# PMactrix.net
KiCad netlist of a schematic drawn in EasyEDA Pro
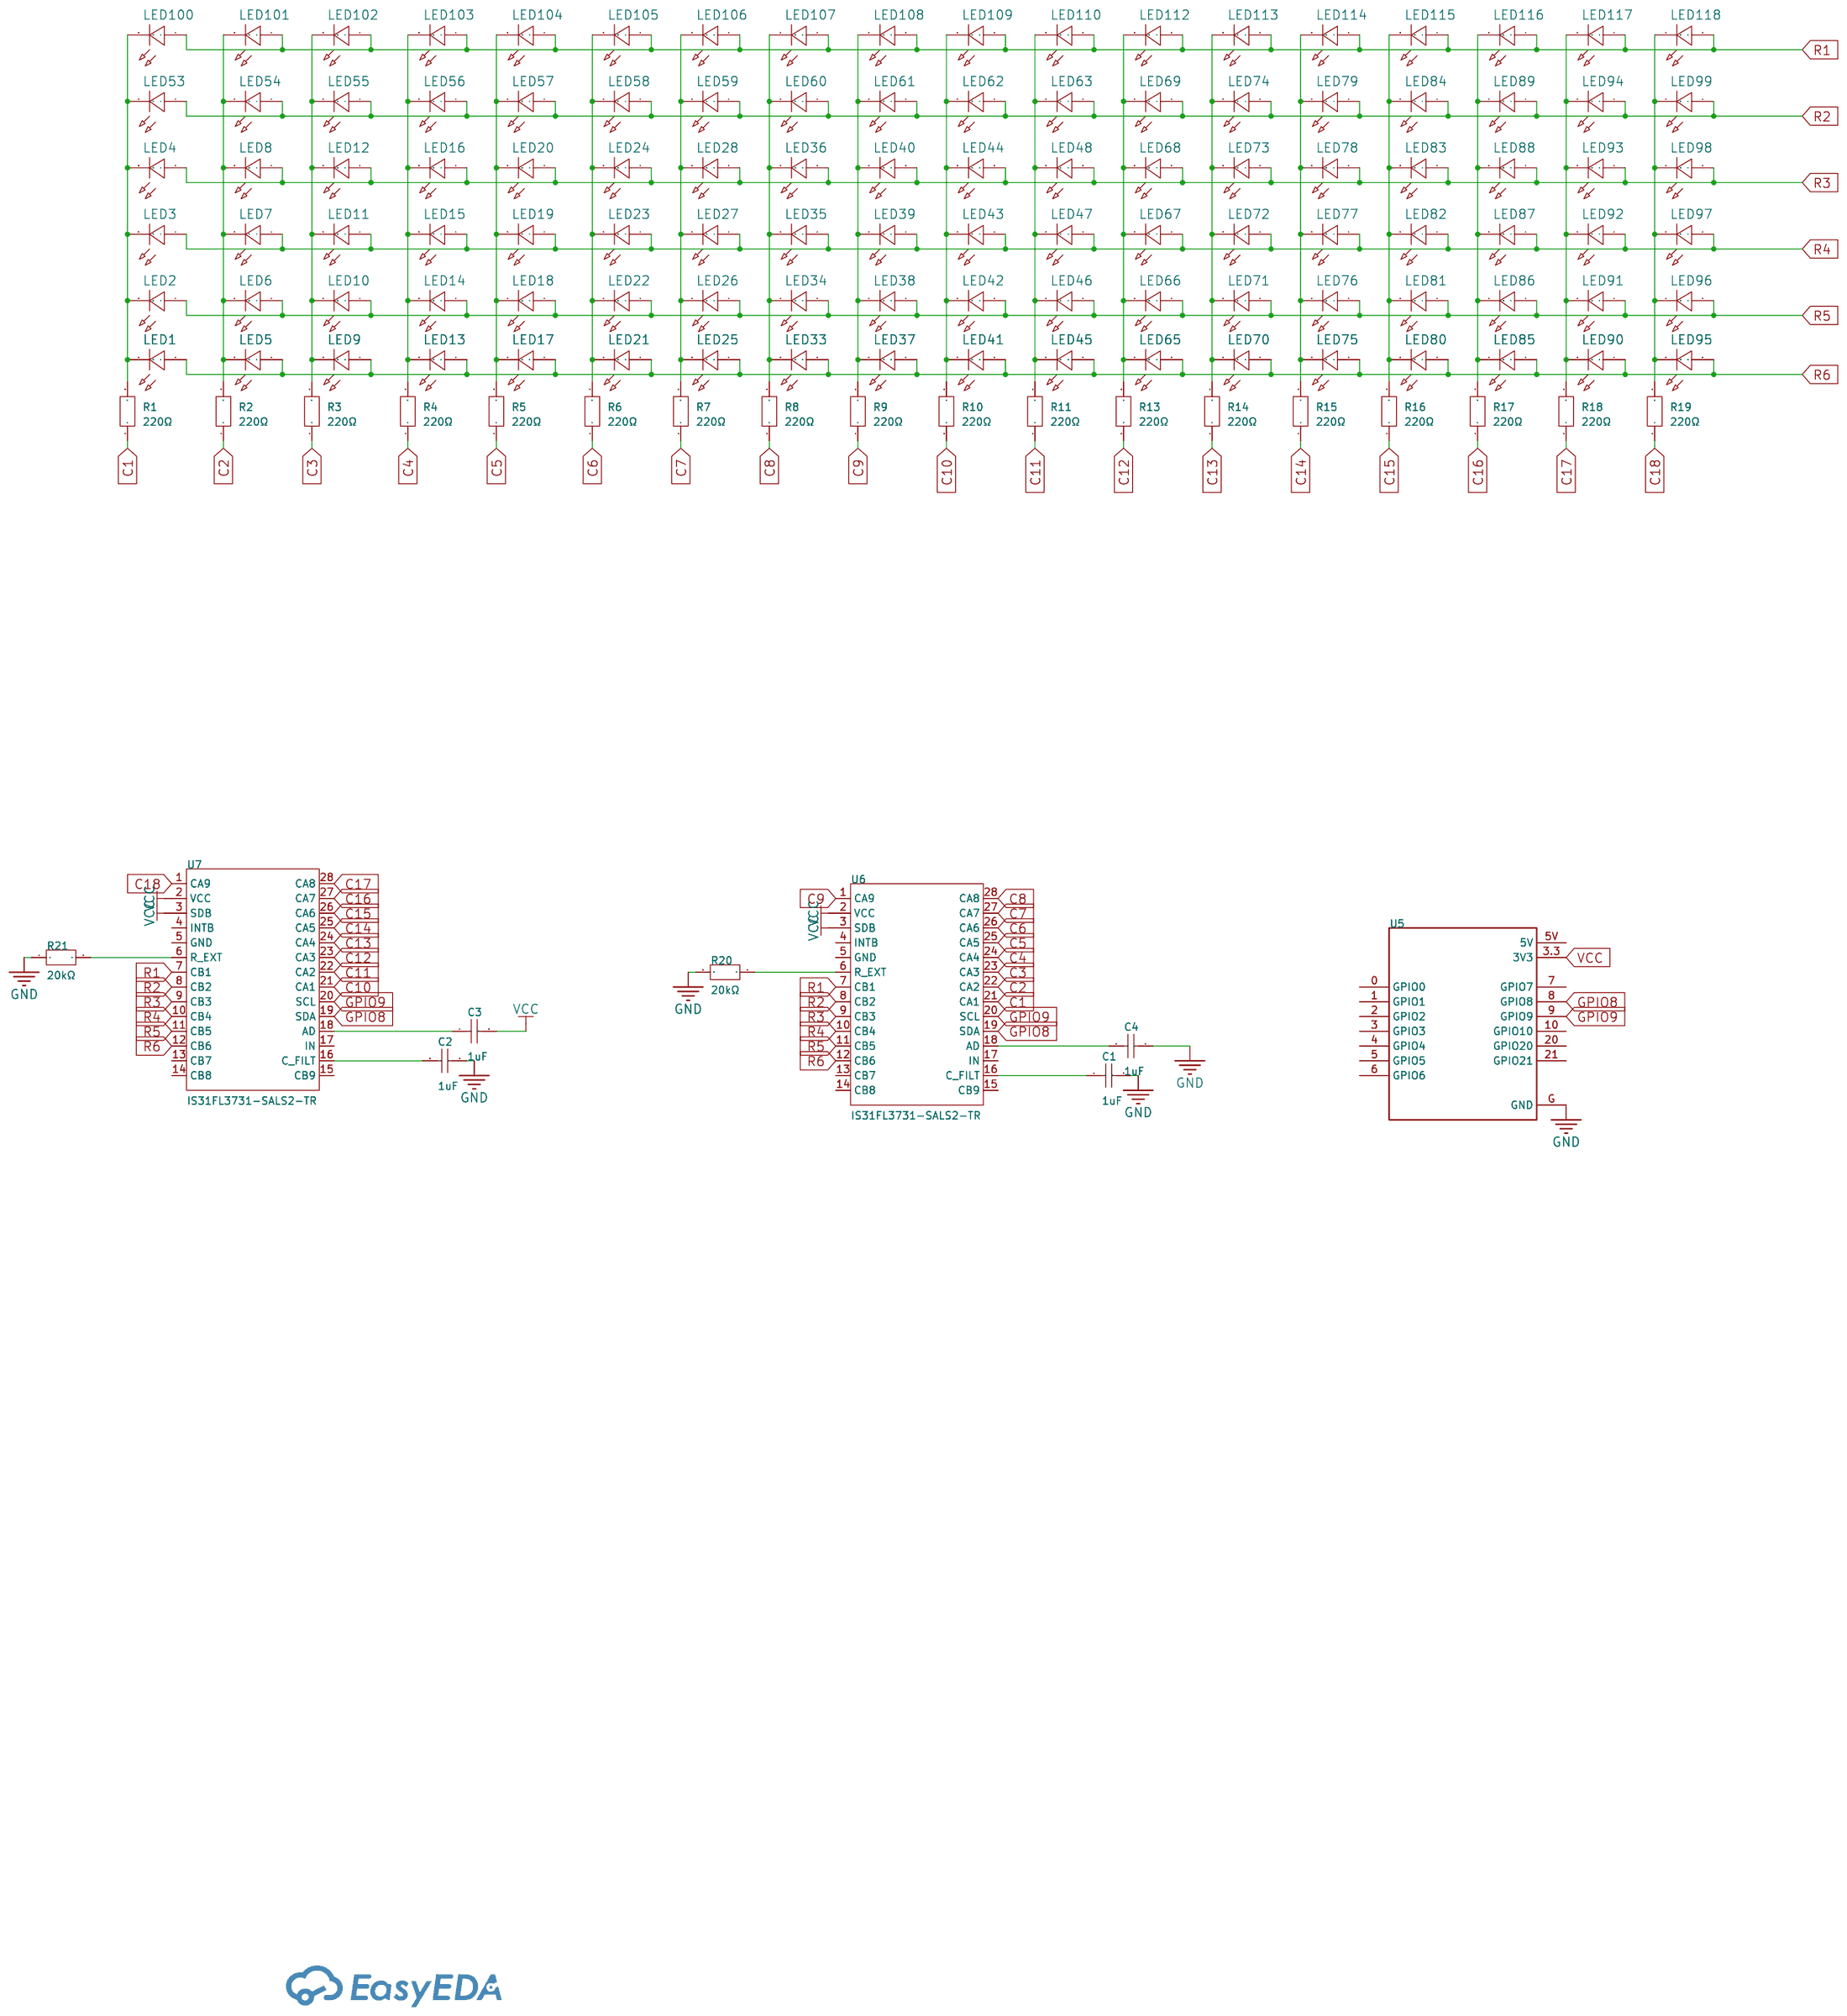
[diagram p0: schematic sheet]

(export (version "E")
  (design (tool "Eeschema 10.0.6"))
  (components
    (comp (ref "C1")
      (value "1uF")
      (footprint "easyedapro:C0603")
      (description "Capacitance:1uF Tolerance:±10% Tolerance:±10% Voltage Rating:25V Temperature Coefficient:X7R")
      (fields
        (field (name "Manufacturer Part") "CL10B105KA8NNNC")
        (field (name "Manufacturer") "SAMSUNG(三星)")
      )
      (libsource (lib "easyedapro") (part "CL10B105KA8NNNC"))
    )
    (comp (ref "C2")
      (value "1uF")
      (footprint "easyedapro:C0603")
      (description "Capacitance:1uF Tolerance:±10% Tolerance:±10% Voltage Rating:25V Temperature Coefficient:X7R")
      (fields
        (field (name "Manufacturer Part") "CL10B105KA8NNNC")
        (field (name "Manufacturer") "SAMSUNG(三星)")
      )
      (libsource (lib "easyedapro") (part "CL10B105KA8NNNC"))
    )
    (comp (ref "C3")
      (value "1uF")
      (footprint "easyedapro:C0603")
      (description "Capacitance:1uF Tolerance:±10% Tolerance:±10% Voltage Rating:25V Temperature Coefficient:X7R")
      (fields
        (field (name "Manufacturer Part") "CL10B105KA8NNNC")
        (field (name "Manufacturer") "SAMSUNG(三星)")
      )
      (libsource (lib "easyedapro") (part "CL10B105KA8NNNC"))
    )
    (comp (ref "C4")
      (value "1uF")
      (footprint "easyedapro:C0603")
      (description "Capacitance:1uF Tolerance:±10% Tolerance:±10% Voltage Rating:25V Temperature Coefficient:X7R")
      (fields
        (field (name "Manufacturer Part") "CL10B105KA8NNNC")
        (field (name "Manufacturer") "SAMSUNG(三星)")
      )
      (libsource (lib "easyedapro") (part "CL10B105KA8NNNC"))
    )
    (comp (ref "LED1")
      (value "SZYY0603W")
      (footprint "easyedapro:LED0402-RD_YELLOW")
      (fields (field (name "Manufacturer") "yongyu(永裕光电)"))
      (libsource (lib "easyedapro") (part "LED_R"))
    )
    (comp (ref "LED2")
      (value "SZYY0603W")
      (footprint "easyedapro:LED0402-RD_YELLOW")
      (fields (field (name "Manufacturer") "yongyu(永裕光电)"))
      (libsource (lib "easyedapro") (part "LED_R"))
    )
    (comp (ref "LED3")
      (value "SZYY0603W")
      (footprint "easyedapro:LED0402-RD_YELLOW")
      (fields (field (name "Manufacturer") "yongyu(永裕光电)"))
      (libsource (lib "easyedapro") (part "LED_R"))
    )
    (comp (ref "LED4")
      (value "SZYY0603W")
      (footprint "easyedapro:LED0402-RD_YELLOW")
      (fields (field (name "Manufacturer") "yongyu(永裕光电)"))
      (libsource (lib "easyedapro") (part "LED_R"))
    )
    (comp (ref "LED5")
      (value "SZYY0603W")
      (footprint "easyedapro:LED0402-RD_YELLOW")
      (fields (field (name "Manufacturer") "yongyu(永裕光电)"))
      (libsource (lib "easyedapro") (part "LED_R"))
    )
    (comp (ref "LED6")
      (value "SZYY0603W")
      (footprint "easyedapro:LED0402-RD_YELLOW")
      (fields (field (name "Manufacturer") "yongyu(永裕光电)"))
      (libsource (lib "easyedapro") (part "LED_R"))
    )
    (comp (ref "LED7")
      (value "SZYY0603W")
      (footprint "easyedapro:LED0402-RD_YELLOW")
      (fields (field (name "Manufacturer") "yongyu(永裕光电)"))
      (libsource (lib "easyedapro") (part "LED_R"))
    )
    (comp (ref "LED8")
      (value "SZYY0603W")
      (footprint "easyedapro:LED0402-RD_YELLOW")
      (fields (field (name "Manufacturer") "yongyu(永裕光电)"))
      (libsource (lib "easyedapro") (part "LED_R"))
    )
    (comp (ref "LED9")
      (value "SZYY0603W")
      (footprint "easyedapro:LED0402-RD_YELLOW")
      (fields (field (name "Manufacturer") "yongyu(永裕光电)"))
      (libsource (lib "easyedapro") (part "LED_R"))
    )
    (comp (ref "LED10")
      (value "SZYY0603W")
      (footprint "easyedapro:LED0402-RD_YELLOW")
      (fields (field (name "Manufacturer") "yongyu(永裕光电)"))
      (libsource (lib "easyedapro") (part "LED_R"))
    )
    (comp (ref "LED11")
      (value "SZYY0603W")
      (footprint "easyedapro:LED0402-RD_YELLOW")
      (fields (field (name "Manufacturer") "yongyu(永裕光电)"))
      (libsource (lib "easyedapro") (part "LED_R"))
    )
    (comp (ref "LED12")
      (value "SZYY0603W")
      (footprint "easyedapro:LED0402-RD_YELLOW")
      (fields (field (name "Manufacturer") "yongyu(永裕光电)"))
      (libsource (lib "easyedapro") (part "LED_R"))
    )
    (comp (ref "LED13")
      (value "SZYY0603W")
      (footprint "easyedapro:LED0402-RD_YELLOW")
      (fields (field (name "Manufacturer") "yongyu(永裕光电)"))
      (libsource (lib "easyedapro") (part "LED_R"))
    )
    (comp (ref "LED14")
      (value "SZYY0603W")
      (footprint "easyedapro:LED0402-RD_YELLOW")
      (fields (field (name "Manufacturer") "yongyu(永裕光电)"))
      (libsource (lib "easyedapro") (part "LED_R"))
    )
    (comp (ref "LED15")
      (value "SZYY0603W")
      (footprint "easyedapro:LED0402-RD_YELLOW")
      (fields (field (name "Manufacturer") "yongyu(永裕光电)"))
      (libsource (lib "easyedapro") (part "LED_R"))
    )
    (comp (ref "LED16")
      (value "SZYY0603W")
      (footprint "easyedapro:LED0402-RD_YELLOW")
      (fields (field (name "Manufacturer") "yongyu(永裕光电)"))
      (libsource (lib "easyedapro") (part "LED_R"))
    )
    (comp (ref "LED17")
      (value "SZYY0603W")
      (footprint "easyedapro:LED0402-RD_YELLOW")
      (fields (field (name "Manufacturer") "yongyu(永裕光电)"))
      (libsource (lib "easyedapro") (part "LED_R"))
    )
    (comp (ref "LED18")
      (value "SZYY0603W")
      (footprint "easyedapro:LED0402-RD_YELLOW")
      (fields (field (name "Manufacturer") "yongyu(永裕光电)"))
      (libsource (lib "easyedapro") (part "LED_R"))
    )
    (comp (ref "LED19")
      (value "SZYY0603W")
      (footprint "easyedapro:LED0402-RD_YELLOW")
      (fields (field (name "Manufacturer") "yongyu(永裕光电)"))
      (libsource (lib "easyedapro") (part "LED_R"))
    )
    (comp (ref "LED20")
      (value "SZYY0603W")
      (footprint "easyedapro:LED0402-RD_YELLOW")
      (fields (field (name "Manufacturer") "yongyu(永裕光电)"))
      (libsource (lib "easyedapro") (part "LED_R"))
    )
    (comp (ref "LED21")
      (value "SZYY0603W")
      (footprint "easyedapro:LED0402-RD_YELLOW")
      (fields (field (name "Manufacturer") "yongyu(永裕光电)"))
      (libsource (lib "easyedapro") (part "LED_R"))
    )
    (comp (ref "LED22")
      (value "SZYY0603W")
      (footprint "easyedapro:LED0402-RD_YELLOW")
      (fields (field (name "Manufacturer") "yongyu(永裕光电)"))
      (libsource (lib "easyedapro") (part "LED_R"))
    )
    (comp (ref "LED23")
      (value "SZYY0603W")
      (footprint "easyedapro:LED0402-RD_YELLOW")
      (fields (field (name "Manufacturer") "yongyu(永裕光电)"))
      (libsource (lib "easyedapro") (part "LED_R"))
    )
    (comp (ref "LED24")
      (value "SZYY0603W")
      (footprint "easyedapro:LED0402-RD_YELLOW")
      (fields (field (name "Manufacturer") "yongyu(永裕光电)"))
      (libsource (lib "easyedapro") (part "LED_R"))
    )
    (comp (ref "LED25")
      (value "SZYY0603W")
      (footprint "easyedapro:LED0402-RD_YELLOW")
      (fields (field (name "Manufacturer") "yongyu(永裕光电)"))
      (libsource (lib "easyedapro") (part "LED_R"))
    )
    (comp (ref "LED26")
      (value "SZYY0603W")
      (footprint "easyedapro:LED0402-RD_YELLOW")
      (fields (field (name "Manufacturer") "yongyu(永裕光电)"))
      (libsource (lib "easyedapro") (part "LED_R"))
    )
    (comp (ref "LED27")
      (value "SZYY0603W")
      (footprint "easyedapro:LED0402-RD_YELLOW")
      (fields (field (name "Manufacturer") "yongyu(永裕光电)"))
      (libsource (lib "easyedapro") (part "LED_R"))
    )
    (comp (ref "LED28")
      (value "SZYY0603W")
      (footprint "easyedapro:LED0402-RD_YELLOW")
      (fields (field (name "Manufacturer") "yongyu(永裕光电)"))
      (libsource (lib "easyedapro") (part "LED_R"))
    )
    (comp (ref "LED33")
      (value "SZYY0603W")
      (footprint "easyedapro:LED0402-RD_YELLOW")
      (fields (field (name "Manufacturer") "yongyu(永裕光电)"))
      (libsource (lib "easyedapro") (part "LED_R"))
    )
    (comp (ref "LED34")
      (value "SZYY0603W")
      (footprint "easyedapro:LED0402-RD_YELLOW")
      (fields (field (name "Manufacturer") "yongyu(永裕光电)"))
      (libsource (lib "easyedapro") (part "LED_R"))
    )
    (comp (ref "LED35")
      (value "SZYY0603W")
      (footprint "easyedapro:LED0402-RD_YELLOW")
      (fields (field (name "Manufacturer") "yongyu(永裕光电)"))
      (libsource (lib "easyedapro") (part "LED_R"))
    )
    (comp (ref "LED36")
      (value "SZYY0603W")
      (footprint "easyedapro:LED0402-RD_YELLOW")
      (fields (field (name "Manufacturer") "yongyu(永裕光电)"))
      (libsource (lib "easyedapro") (part "LED_R"))
    )
    (comp (ref "LED37")
      (value "SZYY0603W")
      (footprint "easyedapro:LED0402-RD_YELLOW")
      (fields (field (name "Manufacturer") "yongyu(永裕光电)"))
      (libsource (lib "easyedapro") (part "LED_R"))
    )
    (comp (ref "LED38")
      (value "SZYY0603W")
      (footprint "easyedapro:LED0402-RD_YELLOW")
      (fields (field (name "Manufacturer") "yongyu(永裕光电)"))
      (libsource (lib "easyedapro") (part "LED_R"))
    )
    (comp (ref "LED39")
      (value "SZYY0603W")
      (footprint "easyedapro:LED0402-RD_YELLOW")
      (fields (field (name "Manufacturer") "yongyu(永裕光电)"))
      (libsource (lib "easyedapro") (part "LED_R"))
    )
    (comp (ref "LED40")
      (value "SZYY0603W")
      (footprint "easyedapro:LED0402-RD_YELLOW")
      (fields (field (name "Manufacturer") "yongyu(永裕光电)"))
      (libsource (lib "easyedapro") (part "LED_R"))
    )
    (comp (ref "LED41")
      (value "SZYY0603W")
      (footprint "easyedapro:LED0402-RD_YELLOW")
      (fields (field (name "Manufacturer") "yongyu(永裕光电)"))
      (libsource (lib "easyedapro") (part "LED_R"))
    )
    (comp (ref "LED42")
      (value "SZYY0603W")
      (footprint "easyedapro:LED0402-RD_YELLOW")
      (fields (field (name "Manufacturer") "yongyu(永裕光电)"))
      (libsource (lib "easyedapro") (part "LED_R"))
    )
    (comp (ref "LED43")
      (value "SZYY0603W")
      (footprint "easyedapro:LED0402-RD_YELLOW")
      (fields (field (name "Manufacturer") "yongyu(永裕光电)"))
      (libsource (lib "easyedapro") (part "LED_R"))
    )
    (comp (ref "LED44")
      (value "SZYY0603W")
      (footprint "easyedapro:LED0402-RD_YELLOW")
      (fields (field (name "Manufacturer") "yongyu(永裕光电)"))
      (libsource (lib "easyedapro") (part "LED_R"))
    )
    (comp (ref "LED45")
      (value "SZYY0603W")
      (footprint "easyedapro:LED0402-RD_YELLOW")
      (fields (field (name "Manufacturer") "yongyu(永裕光电)"))
      (libsource (lib "easyedapro") (part "LED_R"))
    )
    (comp (ref "LED46")
      (value "SZYY0603W")
      (footprint "easyedapro:LED0402-RD_YELLOW")
      (fields (field (name "Manufacturer") "yongyu(永裕光电)"))
      (libsource (lib "easyedapro") (part "LED_R"))
    )
    (comp (ref "LED47")
      (value "SZYY0603W")
      (footprint "easyedapro:LED0402-RD_YELLOW")
      (fields (field (name "Manufacturer") "yongyu(永裕光电)"))
      (libsource (lib "easyedapro") (part "LED_R"))
    )
    (comp (ref "LED48")
      (value "SZYY0603W")
      (footprint "easyedapro:LED0402-RD_YELLOW")
      (fields (field (name "Manufacturer") "yongyu(永裕光电)"))
      (libsource (lib "easyedapro") (part "LED_R"))
    )
    (comp (ref "LED53")
      (value "SZYY0603W")
      (footprint "easyedapro:LED0402-RD_YELLOW")
      (fields (field (name "Manufacturer") "yongyu(永裕光电)"))
      (libsource (lib "easyedapro") (part "LED_R"))
    )
    (comp (ref "LED54")
      (value "SZYY0603W")
      (footprint "easyedapro:LED0402-RD_YELLOW")
      (fields (field (name "Manufacturer") "yongyu(永裕光电)"))
      (libsource (lib "easyedapro") (part "LED_R"))
    )
    (comp (ref "LED55")
      (value "SZYY0603W")
      (footprint "easyedapro:LED0402-RD_YELLOW")
      (fields (field (name "Manufacturer") "yongyu(永裕光电)"))
      (libsource (lib "easyedapro") (part "LED_R"))
    )
    (comp (ref "LED56")
      (value "SZYY0603W")
      (footprint "easyedapro:LED0402-RD_YELLOW")
      (fields (field (name "Manufacturer") "yongyu(永裕光电)"))
      (libsource (lib "easyedapro") (part "LED_R"))
    )
    (comp (ref "LED57")
      (value "SZYY0603W")
      (footprint "easyedapro:LED0402-RD_YELLOW")
      (fields (field (name "Manufacturer") "yongyu(永裕光电)"))
      (libsource (lib "easyedapro") (part "LED_R"))
    )
    (comp (ref "LED58")
      (value "SZYY0603W")
      (footprint "easyedapro:LED0402-RD_YELLOW")
      (fields (field (name "Manufacturer") "yongyu(永裕光电)"))
      (libsource (lib "easyedapro") (part "LED_R"))
    )
    (comp (ref "LED59")
      (value "SZYY0603W")
      (footprint "easyedapro:LED0402-RD_YELLOW")
      (fields (field (name "Manufacturer") "yongyu(永裕光电)"))
      (libsource (lib "easyedapro") (part "LED_R"))
    )
    (comp (ref "LED60")
      (value "SZYY0603W")
      (footprint "easyedapro:LED0402-RD_YELLOW")
      (fields (field (name "Manufacturer") "yongyu(永裕光电)"))
      (libsource (lib "easyedapro") (part "LED_R"))
    )
    (comp (ref "LED61")
      (value "SZYY0603W")
      (footprint "easyedapro:LED0402-RD_YELLOW")
      (fields (field (name "Manufacturer") "yongyu(永裕光电)"))
      (libsource (lib "easyedapro") (part "LED_R"))
    )
    (comp (ref "LED62")
      (value "SZYY0603W")
      (footprint "easyedapro:LED0402-RD_YELLOW")
      (fields (field (name "Manufacturer") "yongyu(永裕光电)"))
      (libsource (lib "easyedapro") (part "LED_R"))
    )
    (comp (ref "LED63")
      (value "SZYY0603W")
      (footprint "easyedapro:LED0402-RD_YELLOW")
      (fields (field (name "Manufacturer") "yongyu(永裕光电)"))
      (libsource (lib "easyedapro") (part "LED_R"))
    )
    (comp (ref "LED65")
      (value "SZYY0603W")
      (footprint "easyedapro:LED0402-RD_YELLOW")
      (fields (field (name "Manufacturer") "yongyu(永裕光电)"))
      (libsource (lib "easyedapro") (part "LED_R"))
    )
    (comp (ref "LED66")
      (value "SZYY0603W")
      (footprint "easyedapro:LED0402-RD_YELLOW")
      (fields (field (name "Manufacturer") "yongyu(永裕光电)"))
      (libsource (lib "easyedapro") (part "LED_R"))
    )
    (comp (ref "LED67")
      (value "SZYY0603W")
      (footprint "easyedapro:LED0402-RD_YELLOW")
      (fields (field (name "Manufacturer") "yongyu(永裕光电)"))
      (libsource (lib "easyedapro") (part "LED_R"))
    )
    (comp (ref "LED68")
      (value "SZYY0603W")
      (footprint "easyedapro:LED0402-RD_YELLOW")
      (fields (field (name "Manufacturer") "yongyu(永裕光电)"))
      (libsource (lib "easyedapro") (part "LED_R"))
    )
    (comp (ref "LED69")
      (value "SZYY0603W")
      (footprint "easyedapro:LED0402-RD_YELLOW")
      (fields (field (name "Manufacturer") "yongyu(永裕光电)"))
      (libsource (lib "easyedapro") (part "LED_R"))
    )
    (comp (ref "LED70")
      (value "SZYY0603W")
      (footprint "easyedapro:LED0402-RD_YELLOW")
      (fields (field (name "Manufacturer") "yongyu(永裕光电)"))
      (libsource (lib "easyedapro") (part "LED_R"))
    )
    (comp (ref "LED71")
      (value "SZYY0603W")
      (footprint "easyedapro:LED0402-RD_YELLOW")
      (fields (field (name "Manufacturer") "yongyu(永裕光电)"))
      (libsource (lib "easyedapro") (part "LED_R"))
    )
    (comp (ref "LED72")
      (value "SZYY0603W")
      (footprint "easyedapro:LED0402-RD_YELLOW")
      (fields (field (name "Manufacturer") "yongyu(永裕光电)"))
      (libsource (lib "easyedapro") (part "LED_R"))
    )
    (comp (ref "LED73")
      (value "SZYY0603W")
      (footprint "easyedapro:LED0402-RD_YELLOW")
      (fields (field (name "Manufacturer") "yongyu(永裕光电)"))
      (libsource (lib "easyedapro") (part "LED_R"))
    )
    (comp (ref "LED74")
      (value "SZYY0603W")
      (footprint "easyedapro:LED0402-RD_YELLOW")
      (fields (field (name "Manufacturer") "yongyu(永裕光电)"))
      (libsource (lib "easyedapro") (part "LED_R"))
    )
    (comp (ref "LED75")
      (value "SZYY0603W")
      (footprint "easyedapro:LED0402-RD_YELLOW")
      (fields (field (name "Manufacturer") "yongyu(永裕光电)"))
      (libsource (lib "easyedapro") (part "LED_R"))
    )
    (comp (ref "LED76")
      (value "SZYY0603W")
      (footprint "easyedapro:LED0402-RD_YELLOW")
      (fields (field (name "Manufacturer") "yongyu(永裕光电)"))
      (libsource (lib "easyedapro") (part "LED_R"))
    )
    (comp (ref "LED77")
      (value "SZYY0603W")
      (footprint "easyedapro:LED0402-RD_YELLOW")
      (fields (field (name "Manufacturer") "yongyu(永裕光电)"))
      (libsource (lib "easyedapro") (part "LED_R"))
    )
    (comp (ref "LED78")
      (value "SZYY0603W")
      (footprint "easyedapro:LED0402-RD_YELLOW")
      (fields (field (name "Manufacturer") "yongyu(永裕光电)"))
      (libsource (lib "easyedapro") (part "LED_R"))
    )
    (comp (ref "LED79")
      (value "SZYY0603W")
      (footprint "easyedapro:LED0402-RD_YELLOW")
      (fields (field (name "Manufacturer") "yongyu(永裕光电)"))
      (libsource (lib "easyedapro") (part "LED_R"))
    )
    (comp (ref "LED80")
      (value "SZYY0603W")
      (footprint "easyedapro:LED0402-RD_YELLOW")
      (fields (field (name "Manufacturer") "yongyu(永裕光电)"))
      (libsource (lib "easyedapro") (part "LED_R"))
    )
    (comp (ref "LED81")
      (value "SZYY0603W")
      (footprint "easyedapro:LED0402-RD_YELLOW")
      (fields (field (name "Manufacturer") "yongyu(永裕光电)"))
      (libsource (lib "easyedapro") (part "LED_R"))
    )
    (comp (ref "LED82")
      (value "SZYY0603W")
      (footprint "easyedapro:LED0402-RD_YELLOW")
      (fields (field (name "Manufacturer") "yongyu(永裕光电)"))
      (libsource (lib "easyedapro") (part "LED_R"))
    )
    (comp (ref "LED83")
      (value "SZYY0603W")
      (footprint "easyedapro:LED0402-RD_YELLOW")
      (fields (field (name "Manufacturer") "yongyu(永裕光电)"))
      (libsource (lib "easyedapro") (part "LED_R"))
    )
    (comp (ref "LED84")
      (value "SZYY0603W")
      (footprint "easyedapro:LED0402-RD_YELLOW")
      (fields (field (name "Manufacturer") "yongyu(永裕光电)"))
      (libsource (lib "easyedapro") (part "LED_R"))
    )
    (comp (ref "LED85")
      (value "SZYY0603W")
      (footprint "easyedapro:LED0402-RD_YELLOW")
      (fields (field (name "Manufacturer") "yongyu(永裕光电)"))
      (libsource (lib "easyedapro") (part "LED_R"))
    )
    (comp (ref "LED86")
      (value "SZYY0603W")
      (footprint "easyedapro:LED0402-RD_YELLOW")
      (fields (field (name "Manufacturer") "yongyu(永裕光电)"))
      (libsource (lib "easyedapro") (part "LED_R"))
    )
    (comp (ref "LED87")
      (value "SZYY0603W")
      (footprint "easyedapro:LED0402-RD_YELLOW")
      (fields (field (name "Manufacturer") "yongyu(永裕光电)"))
      (libsource (lib "easyedapro") (part "LED_R"))
    )
    (comp (ref "LED88")
      (value "SZYY0603W")
      (footprint "easyedapro:LED0402-RD_YELLOW")
      (fields (field (name "Manufacturer") "yongyu(永裕光电)"))
      (libsource (lib "easyedapro") (part "LED_R"))
    )
    (comp (ref "LED89")
      (value "SZYY0603W")
      (footprint "easyedapro:LED0402-RD_YELLOW")
      (fields (field (name "Manufacturer") "yongyu(永裕光电)"))
      (libsource (lib "easyedapro") (part "LED_R"))
    )
    (comp (ref "LED90")
      (value "SZYY0603W")
      (footprint "easyedapro:LED0402-RD_YELLOW")
      (fields (field (name "Manufacturer") "yongyu(永裕光电)"))
      (libsource (lib "easyedapro") (part "LED_R"))
    )
    (comp (ref "LED91")
      (value "SZYY0603W")
      (footprint "easyedapro:LED0402-RD_YELLOW")
      (fields (field (name "Manufacturer") "yongyu(永裕光电)"))
      (libsource (lib "easyedapro") (part "LED_R"))
    )
    (comp (ref "LED92")
      (value "SZYY0603W")
      (footprint "easyedapro:LED0402-RD_YELLOW")
      (fields (field (name "Manufacturer") "yongyu(永裕光电)"))
      (libsource (lib "easyedapro") (part "LED_R"))
    )
    (comp (ref "LED93")
      (value "SZYY0603W")
      (footprint "easyedapro:LED0402-RD_YELLOW")
      (fields (field (name "Manufacturer") "yongyu(永裕光电)"))
      (libsource (lib "easyedapro") (part "LED_R"))
    )
    (comp (ref "LED94")
      (value "SZYY0603W")
      (footprint "easyedapro:LED0402-RD_YELLOW")
      (fields (field (name "Manufacturer") "yongyu(永裕光电)"))
      (libsource (lib "easyedapro") (part "LED_R"))
    )
    (comp (ref "LED95")
      (value "SZYY0603W")
      (footprint "easyedapro:LED0402-RD_YELLOW")
      (fields (field (name "Manufacturer") "yongyu(永裕光电)"))
      (libsource (lib "easyedapro") (part "LED_R"))
    )
    (comp (ref "LED96")
      (value "SZYY0603W")
      (footprint "easyedapro:LED0402-RD_YELLOW")
      (fields (field (name "Manufacturer") "yongyu(永裕光电)"))
      (libsource (lib "easyedapro") (part "LED_R"))
    )
    (comp (ref "LED97")
      (value "SZYY0603W")
      (footprint "easyedapro:LED0402-RD_YELLOW")
      (fields (field (name "Manufacturer") "yongyu(永裕光电)"))
      (libsource (lib "easyedapro") (part "LED_R"))
    )
    (comp (ref "LED98")
      (value "SZYY0603W")
      (footprint "easyedapro:LED0402-RD_YELLOW")
      (fields (field (name "Manufacturer") "yongyu(永裕光电)"))
      (libsource (lib "easyedapro") (part "LED_R"))
    )
    (comp (ref "LED99")
      (value "SZYY0603W")
      (footprint "easyedapro:LED0402-RD_YELLOW")
      (fields (field (name "Manufacturer") "yongyu(永裕光电)"))
      (libsource (lib "easyedapro") (part "LED_R"))
    )
    (comp (ref "LED100")
      (value "SZYY0603W")
      (footprint "easyedapro:LED0402-RD_YELLOW")
      (fields (field (name "Manufacturer") "yongyu(永裕光电)"))
      (libsource (lib "easyedapro") (part "LED_R"))
    )
    (comp (ref "LED101")
      (value "SZYY0603W")
      (footprint "easyedapro:LED0402-RD_YELLOW")
      (fields (field (name "Manufacturer") "yongyu(永裕光电)"))
      (libsource (lib "easyedapro") (part "LED_R"))
    )
    (comp (ref "LED102")
      (value "SZYY0603W")
      (footprint "easyedapro:LED0402-RD_YELLOW")
      (fields (field (name "Manufacturer") "yongyu(永裕光电)"))
      (libsource (lib "easyedapro") (part "LED_R"))
    )
    (comp (ref "LED103")
      (value "SZYY0603W")
      (footprint "easyedapro:LED0402-RD_YELLOW")
      (fields (field (name "Manufacturer") "yongyu(永裕光电)"))
      (libsource (lib "easyedapro") (part "LED_R"))
    )
    (comp (ref "LED104")
      (value "SZYY0603W")
      (footprint "easyedapro:LED0402-RD_YELLOW")
      (fields (field (name "Manufacturer") "yongyu(永裕光电)"))
      (libsource (lib "easyedapro") (part "LED_R"))
    )
    (comp (ref "LED105")
      (value "SZYY0603W")
      (footprint "easyedapro:LED0402-RD_YELLOW")
      (fields (field (name "Manufacturer") "yongyu(永裕光电)"))
      (libsource (lib "easyedapro") (part "LED_R"))
    )
    (comp (ref "LED106")
      (value "SZYY0603W")
      (footprint "easyedapro:LED0402-RD_YELLOW")
      (fields (field (name "Manufacturer") "yongyu(永裕光电)"))
      (libsource (lib "easyedapro") (part "LED_R"))
    )
    (comp (ref "LED107")
      (value "SZYY0603W")
      (footprint "easyedapro:LED0402-RD_YELLOW")
      (fields (field (name "Manufacturer") "yongyu(永裕光电)"))
      (libsource (lib "easyedapro") (part "LED_R"))
    )
    (comp (ref "LED108")
      (value "SZYY0603W")
      (footprint "easyedapro:LED0402-RD_YELLOW")
      (fields (field (name "Manufacturer") "yongyu(永裕光电)"))
      (libsource (lib "easyedapro") (part "LED_R"))
    )
    (comp (ref "LED109")
      (value "SZYY0603W")
      (footprint "easyedapro:LED0402-RD_YELLOW")
      (fields (field (name "Manufacturer") "yongyu(永裕光电)"))
      (libsource (lib "easyedapro") (part "LED_R"))
    )
    (comp (ref "LED110")
      (value "SZYY0603W")
      (footprint "easyedapro:LED0402-RD_YELLOW")
      (fields (field (name "Manufacturer") "yongyu(永裕光电)"))
      (libsource (lib "easyedapro") (part "LED_R"))
    )
    (comp (ref "LED112")
      (value "SZYY0603W")
      (footprint "easyedapro:LED0402-RD_YELLOW")
      (fields (field (name "Manufacturer") "yongyu(永裕光电)"))
      (libsource (lib "easyedapro") (part "LED_R"))
    )
    (comp (ref "LED113")
      (value "SZYY0603W")
      (footprint "easyedapro:LED0402-RD_YELLOW")
      (fields (field (name "Manufacturer") "yongyu(永裕光电)"))
      (libsource (lib "easyedapro") (part "LED_R"))
    )
    (comp (ref "LED114")
      (value "SZYY0603W")
      (footprint "easyedapro:LED0402-RD_YELLOW")
      (fields (field (name "Manufacturer") "yongyu(永裕光电)"))
      (libsource (lib "easyedapro") (part "LED_R"))
    )
    (comp (ref "LED115")
      (value "SZYY0603W")
      (footprint "easyedapro:LED0402-RD_YELLOW")
      (fields (field (name "Manufacturer") "yongyu(永裕光电)"))
      (libsource (lib "easyedapro") (part "LED_R"))
    )
    (comp (ref "LED116")
      (value "SZYY0603W")
      (footprint "easyedapro:LED0402-RD_YELLOW")
      (fields (field (name "Manufacturer") "yongyu(永裕光电)"))
      (libsource (lib "easyedapro") (part "LED_R"))
    )
    (comp (ref "LED117")
      (value "SZYY0603W")
      (footprint "easyedapro:LED0402-RD_YELLOW")
      (fields (field (name "Manufacturer") "yongyu(永裕光电)"))
      (libsource (lib "easyedapro") (part "LED_R"))
    )
    (comp (ref "LED118")
      (value "SZYY0603W")
      (footprint "easyedapro:LED0402-RD_YELLOW")
      (fields (field (name "Manufacturer") "yongyu(永裕光电)"))
      (libsource (lib "easyedapro") (part "LED_R"))
    )
    (comp (ref "R1")
      (value "220Ω")
      (footprint "easyedapro:R0603")
      (fields
        (field (name "Manufacturer Part") "CR0603F220RP05Z")
        (field (name "Manufacturer") "EVER OHMS(天二科技)")
      )
      (libsource (lib "easyedapro") (part "CR0603F220RP05Z"))
    )
    (comp (ref "R2")
      (value "220Ω")
      (footprint "easyedapro:R0603")
      (fields
        (field (name "Manufacturer Part") "CR0603F220RP05Z")
        (field (name "Manufacturer") "EVER OHMS(天二科技)")
      )
      (libsource (lib "easyedapro") (part "CR0603F220RP05Z"))
    )
    (comp (ref "R3")
      (value "220Ω")
      (footprint "easyedapro:R0603")
      (fields
        (field (name "Manufacturer Part") "CR0603F220RP05Z")
        (field (name "Manufacturer") "EVER OHMS(天二科技)")
      )
      (libsource (lib "easyedapro") (part "CR0603F220RP05Z"))
    )
    (comp (ref "R4")
      (value "220Ω")
      (footprint "easyedapro:R0603")
      (fields
        (field (name "Manufacturer Part") "CR0603F220RP05Z")
        (field (name "Manufacturer") "EVER OHMS(天二科技)")
      )
      (libsource (lib "easyedapro") (part "CR0603F220RP05Z"))
    )
    (comp (ref "R5")
      (value "220Ω")
      (footprint "easyedapro:R0603")
      (fields
        (field (name "Manufacturer Part") "CR0603F220RP05Z")
        (field (name "Manufacturer") "EVER OHMS(天二科技)")
      )
      (libsource (lib "easyedapro") (part "CR0603F220RP05Z"))
    )
    (comp (ref "R6")
      (value "220Ω")
      (footprint "easyedapro:R0603")
      (fields
        (field (name "Manufacturer Part") "CR0603F220RP05Z")
        (field (name "Manufacturer") "EVER OHMS(天二科技)")
      )
      (libsource (lib "easyedapro") (part "CR0603F220RP05Z"))
    )
    (comp (ref "R7")
      (value "220Ω")
      (footprint "easyedapro:R0603")
      (fields
        (field (name "Manufacturer Part") "CR0603F220RP05Z")
        (field (name "Manufacturer") "EVER OHMS(天二科技)")
      )
      (libsource (lib "easyedapro") (part "CR0603F220RP05Z"))
    )
    (comp (ref "R8")
      (value "220Ω")
      (footprint "easyedapro:R0603")
      (fields
        (field (name "Manufacturer Part") "CR0603F220RP05Z")
        (field (name "Manufacturer") "EVER OHMS(天二科技)")
      )
      (libsource (lib "easyedapro") (part "CR0603F220RP05Z"))
    )
    (comp (ref "R9")
      (value "220Ω")
      (footprint "easyedapro:R0603")
      (fields
        (field (name "Manufacturer Part") "CR0603F220RP05Z")
        (field (name "Manufacturer") "EVER OHMS(天二科技)")
      )
      (libsource (lib "easyedapro") (part "CR0603F220RP05Z"))
    )
    (comp (ref "R10")
      (value "220Ω")
      (footprint "easyedapro:R0603")
      (fields
        (field (name "Manufacturer Part") "CR0603F220RP05Z")
        (field (name "Manufacturer") "EVER OHMS(天二科技)")
      )
      (libsource (lib "easyedapro") (part "CR0603F220RP05Z"))
    )
    (comp (ref "R11")
      (value "220Ω")
      (footprint "easyedapro:R0603")
      (fields
        (field (name "Manufacturer Part") "CR0603F220RP05Z")
        (field (name "Manufacturer") "EVER OHMS(天二科技)")
      )
      (libsource (lib "easyedapro") (part "CR0603F220RP05Z"))
    )
    (comp (ref "R13")
      (value "220Ω")
      (footprint "easyedapro:R0603")
      (fields
        (field (name "Manufacturer Part") "CR0603F220RP05Z")
        (field (name "Manufacturer") "EVER OHMS(天二科技)")
      )
      (libsource (lib "easyedapro") (part "CR0603F220RP05Z"))
    )
    (comp (ref "R14")
      (value "220Ω")
      (footprint "easyedapro:R0603")
      (fields
        (field (name "Manufacturer Part") "CR0603F220RP05Z")
        (field (name "Manufacturer") "EVER OHMS(天二科技)")
      )
      (libsource (lib "easyedapro") (part "CR0603F220RP05Z"))
    )
    (comp (ref "R15")
      (value "220Ω")
      (footprint "easyedapro:R0603")
      (fields
        (field (name "Manufacturer Part") "CR0603F220RP05Z")
        (field (name "Manufacturer") "EVER OHMS(天二科技)")
      )
      (libsource (lib "easyedapro") (part "CR0603F220RP05Z"))
    )
    (comp (ref "R16")
      (value "220Ω")
      (footprint "easyedapro:R0603")
      (fields
        (field (name "Manufacturer Part") "CR0603F220RP05Z")
        (field (name "Manufacturer") "EVER OHMS(天二科技)")
      )
      (libsource (lib "easyedapro") (part "CR0603F220RP05Z"))
    )
    (comp (ref "R17")
      (value "220Ω")
      (footprint "easyedapro:R0603")
      (fields
        (field (name "Manufacturer Part") "CR0603F220RP05Z")
        (field (name "Manufacturer") "EVER OHMS(天二科技)")
      )
      (libsource (lib "easyedapro") (part "CR0603F220RP05Z"))
    )
    (comp (ref "R18")
      (value "220Ω")
      (footprint "easyedapro:R0603")
      (fields
        (field (name "Manufacturer Part") "CR0603F220RP05Z")
        (field (name "Manufacturer") "EVER OHMS(天二科技)")
      )
      (libsource (lib "easyedapro") (part "CR0603F220RP05Z"))
    )
    (comp (ref "R19")
      (value "220Ω")
      (footprint "easyedapro:R0603")
      (fields
        (field (name "Manufacturer Part") "CR0603F220RP05Z")
        (field (name "Manufacturer") "EVER OHMS(天二科技)")
      )
      (libsource (lib "easyedapro") (part "CR0603F220RP05Z"))
    )
    (comp (ref "R20")
      (value "20kΩ")
      (footprint "easyedapro:R0603")
      (fields (field (name "Manufacturer Part") "FRC0603F2002TS") (field (name "Manufacturer") "FOJAN(富捷)"))
      (libsource (lib "easyedapro") (part "FRC0603F2002TS"))
    )
    (comp (ref "R21")
      (value "20kΩ")
      (footprint "easyedapro:R0603")
      (fields (field (name "Manufacturer Part") "FRC0603F2002TS") (field (name "Manufacturer") "FOJAN(富捷)"))
      (libsource (lib "easyedapro") (part "FRC0603F2002TS"))
    )
    (comp (ref "U5")
      (value "~")
      (footprint "easyedapro:MODULE_ESP32-C3_SUPERMINI_TH")
      (libsource (lib "easyedapro") (part "ESP32-C3_SUPERMINI 1"))
    )
    (comp (ref "U6")
      (value "IS31FL3731-SALS2-TR")
      (footprint "easyedapro:SSOP-28_L10.2-W5.3-P0.65-LS7.8-BL")
      (fields (field (name "Manufacturer") "ISSI(美国芯成)"))
      (libsource (lib "easyedapro") (part "IS31FL3731-SALS2-TR"))
    )
    (comp (ref "U7")
      (value "IS31FL3731-SALS2-TR")
      (footprint "easyedapro:SSOP-28_L10.2-W5.3-P0.65-LS7.8-BL")
      (fields (field (name "Manufacturer") "ISSI(美国芯成)"))
      (libsource (lib "easyedapro") (part "IS31FL3731-SALS2-TR"))
    )
  )
  (nets
    (net (code "1") (name "C1") (class "Default")
      (node (ref "R1") (pin "1") (pinfunction "1_1") (pintype "unspecified"))
      (node (ref "U6") (pin "21") (pinfunction "CA1_21") (pintype "unspecified"))
    )
    (net (code "2") (name "C2") (class "Default")
      (node (ref "R2") (pin "1") (pinfunction "1_1") (pintype "unspecified"))
      (node (ref "U6") (pin "22") (pinfunction "CA2_22") (pintype "unspecified"))
    )
    (net (code "3") (name "C3") (class "Default")
      (node (ref "R3") (pin "1") (pinfunction "1_1") (pintype "unspecified"))
      (node (ref "U6") (pin "23") (pinfunction "CA3_23") (pintype "unspecified"))
    )
    (net (code "4") (name "C4") (class "Default")
      (node (ref "R4") (pin "1") (pinfunction "1_1") (pintype "unspecified"))
      (node (ref "U6") (pin "24") (pinfunction "CA4_24") (pintype "unspecified"))
    )
    (net (code "5") (name "C5") (class "Default")
      (node (ref "R5") (pin "1") (pinfunction "1_1") (pintype "unspecified"))
      (node (ref "U6") (pin "25") (pinfunction "CA5_25") (pintype "unspecified"))
    )
    (net (code "6") (name "C6") (class "Default")
      (node (ref "R6") (pin "1") (pinfunction "1_1") (pintype "unspecified"))
      (node (ref "U6") (pin "26") (pinfunction "CA6_26") (pintype "unspecified"))
    )
    (net (code "7") (name "C7") (class "Default")
      (node (ref "R7") (pin "1") (pinfunction "1_1") (pintype "unspecified"))
      (node (ref "U6") (pin "27") (pinfunction "CA7_27") (pintype "unspecified"))
    )
    (net (code "8") (name "C8") (class "Default")
      (node (ref "R8") (pin "1") (pinfunction "1_1") (pintype "unspecified"))
      (node (ref "U6") (pin "28") (pinfunction "CA8_28") (pintype "unspecified"))
    )
    (net (code "9") (name "C9") (class "Default")
      (node (ref "R9") (pin "1") (pinfunction "1_1") (pintype "unspecified"))
      (node (ref "U6") (pin "1") (pinfunction "CA9_1") (pintype "unspecified"))
    )
    (net (code "10") (name "C10") (class "Default")
      (node (ref "R10") (pin "1") (pinfunction "1_1") (pintype "unspecified"))
      (node (ref "U7") (pin "21") (pinfunction "CA1_21") (pintype "unspecified"))
    )
    (net (code "11") (name "C11") (class "Default")
      (node (ref "R11") (pin "1") (pinfunction "1_1") (pintype "unspecified"))
      (node (ref "U7") (pin "22") (pinfunction "CA2_22") (pintype "unspecified"))
    )
    (net (code "12") (name "C12") (class "Default")
      (node (ref "R13") (pin "1") (pinfunction "1_1") (pintype "unspecified"))
      (node (ref "U7") (pin "23") (pinfunction "CA3_23") (pintype "unspecified"))
    )
    (net (code "13") (name "C13") (class "Default")
      (node (ref "R14") (pin "1") (pinfunction "1_1") (pintype "unspecified"))
      (node (ref "U7") (pin "24") (pinfunction "CA4_24") (pintype "unspecified"))
    )
    (net (code "14") (name "C14") (class "Default")
      (node (ref "R15") (pin "1") (pinfunction "1_1") (pintype "unspecified"))
      (node (ref "U7") (pin "25") (pinfunction "CA5_25") (pintype "unspecified"))
    )
    (net (code "15") (name "C15") (class "Default")
      (node (ref "R16") (pin "1") (pinfunction "1_1") (pintype "unspecified"))
      (node (ref "U7") (pin "26") (pinfunction "CA6_26") (pintype "unspecified"))
    )
    (net (code "16") (name "C16") (class "Default")
      (node (ref "R17") (pin "1") (pinfunction "1_1") (pintype "unspecified"))
      (node (ref "U7") (pin "27") (pinfunction "CA7_27") (pintype "unspecified"))
    )
    (net (code "17") (name "C17") (class "Default")
      (node (ref "R18") (pin "1") (pinfunction "1_1") (pintype "unspecified"))
      (node (ref "U7") (pin "28") (pinfunction "CA8_28") (pintype "unspecified"))
    )
    (net (code "18") (name "C18") (class "Default")
      (node (ref "R19") (pin "1") (pinfunction "1_1") (pintype "unspecified"))
      (node (ref "U7") (pin "1") (pinfunction "CA9_1") (pintype "unspecified"))
    )
    (net (code "19") (name "GND") (class "Default")
      (node (ref "C1") (pin "2") (pinfunction "2_2") (pintype "input"))
      (node (ref "C2") (pin "2") (pinfunction "2_2") (pintype "input"))
      (node (ref "C4") (pin "2") (pinfunction "2_2") (pintype "input"))
      (node (ref "R20") (pin "1") (pinfunction "1_1") (pintype "unspecified"))
      (node (ref "R21") (pin "1") (pinfunction "1_1") (pintype "unspecified"))
      (node (ref "U5") (pin "G") (pinfunction "GND_G") (pintype "unspecified"))
    )
    (net (code "20") (name "GPIO8") (class "Default")
      (node (ref "U5") (pin "8") (pinfunction "GPIO8_8") (pintype "bidirectional"))
      (node (ref "U6") (pin "19") (pinfunction "SDA_19") (pintype "unspecified"))
      (node (ref "U7") (pin "19") (pinfunction "SDA_19") (pintype "unspecified"))
    )
    (net (code "21") (name "GPIO9") (class "Default")
      (node (ref "U5") (pin "9") (pinfunction "GPIO9_9") (pintype "bidirectional"))
      (node (ref "U6") (pin "20") (pinfunction "SCL_20") (pintype "unspecified"))
      (node (ref "U7") (pin "20") (pinfunction "SCL_20") (pintype "unspecified"))
    )
    (net (code "22") (name "Net-(LED1-C)") (class "Default")
      (node (ref "LED1") (pin "2") (pinfunction "C_2") (pintype "input"))
      (node (ref "LED100") (pin "2") (pinfunction "C_2") (pintype "input"))
      (node (ref "LED2") (pin "2") (pinfunction "C_2") (pintype "input"))
      (node (ref "LED3") (pin "2") (pinfunction "C_2") (pintype "input"))
      (node (ref "LED4") (pin "2") (pinfunction "C_2") (pintype "input"))
      (node (ref "LED53") (pin "2") (pinfunction "C_2") (pintype "input"))
      (node (ref "R1") (pin "2") (pinfunction "2_2") (pintype "unspecified"))
    )
    (net (code "23") (name "Net-(LED10-C)") (class "Default")
      (node (ref "LED10") (pin "2") (pinfunction "C_2") (pintype "input"))
      (node (ref "LED102") (pin "2") (pinfunction "C_2") (pintype "input"))
      (node (ref "LED11") (pin "2") (pinfunction "C_2") (pintype "input"))
      (node (ref "LED12") (pin "2") (pinfunction "C_2") (pintype "input"))
      (node (ref "LED55") (pin "2") (pinfunction "C_2") (pintype "input"))
      (node (ref "LED9") (pin "2") (pinfunction "C_2") (pintype "input"))
      (node (ref "R3") (pin "2") (pinfunction "2_2") (pintype "unspecified"))
    )
    (net (code "24") (name "Net-(LED101-C)") (class "Default")
      (node (ref "LED101") (pin "2") (pinfunction "C_2") (pintype "input"))
      (node (ref "LED5") (pin "2") (pinfunction "C_2") (pintype "input"))
      (node (ref "LED54") (pin "2") (pinfunction "C_2") (pintype "input"))
      (node (ref "LED6") (pin "2") (pinfunction "C_2") (pintype "input"))
      (node (ref "LED7") (pin "2") (pinfunction "C_2") (pintype "input"))
      (node (ref "LED8") (pin "2") (pinfunction "C_2") (pintype "input"))
      (node (ref "R2") (pin "2") (pinfunction "2_2") (pintype "unspecified"))
    )
    (net (code "25") (name "Net-(LED103-C)") (class "Default")
      (node (ref "LED103") (pin "2") (pinfunction "C_2") (pintype "input"))
      (node (ref "LED13") (pin "2") (pinfunction "C_2") (pintype "input"))
      (node (ref "LED14") (pin "2") (pinfunction "C_2") (pintype "input"))
      (node (ref "LED15") (pin "2") (pinfunction "C_2") (pintype "input"))
      (node (ref "LED16") (pin "2") (pinfunction "C_2") (pintype "input"))
      (node (ref "LED56") (pin "2") (pinfunction "C_2") (pintype "input"))
      (node (ref "R4") (pin "2") (pinfunction "2_2") (pintype "unspecified"))
    )
    (net (code "26") (name "Net-(LED104-C)") (class "Default")
      (node (ref "LED104") (pin "2") (pinfunction "C_2") (pintype "input"))
      (node (ref "LED17") (pin "2") (pinfunction "C_2") (pintype "input"))
      (node (ref "LED18") (pin "2") (pinfunction "C_2") (pintype "input"))
      (node (ref "LED19") (pin "2") (pinfunction "C_2") (pintype "input"))
      (node (ref "LED20") (pin "2") (pinfunction "C_2") (pintype "input"))
      (node (ref "LED57") (pin "2") (pinfunction "C_2") (pintype "input"))
      (node (ref "R5") (pin "2") (pinfunction "2_2") (pintype "unspecified"))
    )
    (net (code "27") (name "Net-(LED105-C)") (class "Default")
      (node (ref "LED105") (pin "2") (pinfunction "C_2") (pintype "input"))
      (node (ref "LED21") (pin "2") (pinfunction "C_2") (pintype "input"))
      (node (ref "LED22") (pin "2") (pinfunction "C_2") (pintype "input"))
      (node (ref "LED23") (pin "2") (pinfunction "C_2") (pintype "input"))
      (node (ref "LED24") (pin "2") (pinfunction "C_2") (pintype "input"))
      (node (ref "LED58") (pin "2") (pinfunction "C_2") (pintype "input"))
      (node (ref "R6") (pin "2") (pinfunction "2_2") (pintype "unspecified"))
    )
    (net (code "28") (name "Net-(LED106-C)") (class "Default")
      (node (ref "LED106") (pin "2") (pinfunction "C_2") (pintype "input"))
      (node (ref "LED25") (pin "2") (pinfunction "C_2") (pintype "input"))
      (node (ref "LED26") (pin "2") (pinfunction "C_2") (pintype "input"))
      (node (ref "LED27") (pin "2") (pinfunction "C_2") (pintype "input"))
      (node (ref "LED28") (pin "2") (pinfunction "C_2") (pintype "input"))
      (node (ref "LED59") (pin "2") (pinfunction "C_2") (pintype "input"))
      (node (ref "R7") (pin "2") (pinfunction "2_2") (pintype "unspecified"))
    )
    (net (code "29") (name "Net-(LED107-C)") (class "Default")
      (node (ref "LED107") (pin "2") (pinfunction "C_2") (pintype "input"))
      (node (ref "LED33") (pin "2") (pinfunction "C_2") (pintype "input"))
      (node (ref "LED34") (pin "2") (pinfunction "C_2") (pintype "input"))
      (node (ref "LED35") (pin "2") (pinfunction "C_2") (pintype "input"))
      (node (ref "LED36") (pin "2") (pinfunction "C_2") (pintype "input"))
      (node (ref "LED60") (pin "2") (pinfunction "C_2") (pintype "input"))
      (node (ref "R8") (pin "2") (pinfunction "2_2") (pintype "unspecified"))
    )
    (net (code "30") (name "Net-(LED108-C)") (class "Default")
      (node (ref "LED108") (pin "2") (pinfunction "C_2") (pintype "input"))
      (node (ref "LED37") (pin "2") (pinfunction "C_2") (pintype "input"))
      (node (ref "LED38") (pin "2") (pinfunction "C_2") (pintype "input"))
      (node (ref "LED39") (pin "2") (pinfunction "C_2") (pintype "input"))
      (node (ref "LED40") (pin "2") (pinfunction "C_2") (pintype "input"))
      (node (ref "LED61") (pin "2") (pinfunction "C_2") (pintype "input"))
      (node (ref "R9") (pin "2") (pinfunction "2_2") (pintype "unspecified"))
    )
    (net (code "31") (name "Net-(LED109-C)") (class "Default")
      (node (ref "LED109") (pin "2") (pinfunction "C_2") (pintype "input"))
      (node (ref "LED41") (pin "2") (pinfunction "C_2") (pintype "input"))
      (node (ref "LED42") (pin "2") (pinfunction "C_2") (pintype "input"))
      (node (ref "LED43") (pin "2") (pinfunction "C_2") (pintype "input"))
      (node (ref "LED44") (pin "2") (pinfunction "C_2") (pintype "input"))
      (node (ref "LED62") (pin "2") (pinfunction "C_2") (pintype "input"))
      (node (ref "R10") (pin "2") (pinfunction "2_2") (pintype "unspecified"))
    )
    (net (code "32") (name "Net-(LED110-C)") (class "Default")
      (node (ref "LED110") (pin "2") (pinfunction "C_2") (pintype "input"))
      (node (ref "LED45") (pin "2") (pinfunction "C_2") (pintype "input"))
      (node (ref "LED46") (pin "2") (pinfunction "C_2") (pintype "input"))
      (node (ref "LED47") (pin "2") (pinfunction "C_2") (pintype "input"))
      (node (ref "LED48") (pin "2") (pinfunction "C_2") (pintype "input"))
      (node (ref "LED63") (pin "2") (pinfunction "C_2") (pintype "input"))
      (node (ref "R11") (pin "2") (pinfunction "2_2") (pintype "unspecified"))
    )
    (net (code "33") (name "Net-(LED112-C)") (class "Default")
      (node (ref "LED112") (pin "2") (pinfunction "C_2") (pintype "input"))
      (node (ref "LED65") (pin "2") (pinfunction "C_2") (pintype "input"))
      (node (ref "LED66") (pin "2") (pinfunction "C_2") (pintype "input"))
      (node (ref "LED67") (pin "2") (pinfunction "C_2") (pintype "input"))
      (node (ref "LED68") (pin "2") (pinfunction "C_2") (pintype "input"))
      (node (ref "LED69") (pin "2") (pinfunction "C_2") (pintype "input"))
      (node (ref "R13") (pin "2") (pinfunction "2_2") (pintype "unspecified"))
    )
    (net (code "34") (name "Net-(LED113-C)") (class "Default")
      (node (ref "LED113") (pin "2") (pinfunction "C_2") (pintype "input"))
      (node (ref "LED70") (pin "2") (pinfunction "C_2") (pintype "input"))
      (node (ref "LED71") (pin "2") (pinfunction "C_2") (pintype "input"))
      (node (ref "LED72") (pin "2") (pinfunction "C_2") (pintype "input"))
      (node (ref "LED73") (pin "2") (pinfunction "C_2") (pintype "input"))
      (node (ref "LED74") (pin "2") (pinfunction "C_2") (pintype "input"))
      (node (ref "R14") (pin "2") (pinfunction "2_2") (pintype "unspecified"))
    )
    (net (code "35") (name "Net-(LED114-C)") (class "Default")
      (node (ref "LED114") (pin "2") (pinfunction "C_2") (pintype "input"))
      (node (ref "LED75") (pin "2") (pinfunction "C_2") (pintype "input"))
      (node (ref "LED76") (pin "2") (pinfunction "C_2") (pintype "input"))
      (node (ref "LED77") (pin "2") (pinfunction "C_2") (pintype "input"))
      (node (ref "LED78") (pin "2") (pinfunction "C_2") (pintype "input"))
      (node (ref "LED79") (pin "2") (pinfunction "C_2") (pintype "input"))
      (node (ref "R15") (pin "2") (pinfunction "2_2") (pintype "unspecified"))
    )
    (net (code "36") (name "Net-(LED115-C)") (class "Default")
      (node (ref "LED115") (pin "2") (pinfunction "C_2") (pintype "input"))
      (node (ref "LED80") (pin "2") (pinfunction "C_2") (pintype "input"))
      (node (ref "LED81") (pin "2") (pinfunction "C_2") (pintype "input"))
      (node (ref "LED82") (pin "2") (pinfunction "C_2") (pintype "input"))
      (node (ref "LED83") (pin "2") (pinfunction "C_2") (pintype "input"))
      (node (ref "LED84") (pin "2") (pinfunction "C_2") (pintype "input"))
      (node (ref "R16") (pin "2") (pinfunction "2_2") (pintype "unspecified"))
    )
    (net (code "37") (name "Net-(LED116-C)") (class "Default")
      (node (ref "LED116") (pin "2") (pinfunction "C_2") (pintype "input"))
      (node (ref "LED85") (pin "2") (pinfunction "C_2") (pintype "input"))
      (node (ref "LED86") (pin "2") (pinfunction "C_2") (pintype "input"))
      (node (ref "LED87") (pin "2") (pinfunction "C_2") (pintype "input"))
      (node (ref "LED88") (pin "2") (pinfunction "C_2") (pintype "input"))
      (node (ref "LED89") (pin "2") (pinfunction "C_2") (pintype "input"))
      (node (ref "R17") (pin "2") (pinfunction "2_2") (pintype "unspecified"))
    )
    (net (code "38") (name "Net-(LED117-C)") (class "Default")
      (node (ref "LED117") (pin "2") (pinfunction "C_2") (pintype "input"))
      (node (ref "LED90") (pin "2") (pinfunction "C_2") (pintype "input"))
      (node (ref "LED91") (pin "2") (pinfunction "C_2") (pintype "input"))
      (node (ref "LED92") (pin "2") (pinfunction "C_2") (pintype "input"))
      (node (ref "LED93") (pin "2") (pinfunction "C_2") (pintype "input"))
      (node (ref "LED94") (pin "2") (pinfunction "C_2") (pintype "input"))
      (node (ref "R18") (pin "2") (pinfunction "2_2") (pintype "unspecified"))
    )
    (net (code "39") (name "Net-(LED118-C)") (class "Default")
      (node (ref "LED118") (pin "2") (pinfunction "C_2") (pintype "input"))
      (node (ref "LED95") (pin "2") (pinfunction "C_2") (pintype "input"))
      (node (ref "LED96") (pin "2") (pinfunction "C_2") (pintype "input"))
      (node (ref "LED97") (pin "2") (pinfunction "C_2") (pintype "input"))
      (node (ref "LED98") (pin "2") (pinfunction "C_2") (pintype "input"))
      (node (ref "LED99") (pin "2") (pinfunction "C_2") (pintype "input"))
      (node (ref "R19") (pin "2") (pinfunction "2_2") (pintype "unspecified"))
    )
    (net (code "40") (name "Net-(U6-AD)") (class "Default")
      (node (ref "C4") (pin "1") (pinfunction "1_1") (pintype "input"))
      (node (ref "U6") (pin "18") (pinfunction "AD_18") (pintype "unspecified"))
    )
    (net (code "41") (name "Net-(U6-C_FILT)") (class "Default")
      (node (ref "C1") (pin "1") (pinfunction "1_1") (pintype "input"))
      (node (ref "U6") (pin "16") (pinfunction "C_FILT_16") (pintype "unspecified"))
    )
    (net (code "42") (name "Net-(U6-R_EXT)") (class "Default")
      (node (ref "R20") (pin "2") (pinfunction "2_2") (pintype "unspecified"))
      (node (ref "U6") (pin "6") (pinfunction "R_EXT_6") (pintype "unspecified"))
    )
    (net (code "43") (name "Net-(U7-AD)") (class "Default")
      (node (ref "C3") (pin "1") (pinfunction "1_1") (pintype "input"))
      (node (ref "U7") (pin "18") (pinfunction "AD_18") (pintype "unspecified"))
    )
    (net (code "44") (name "Net-(U7-C_FILT)") (class "Default")
      (node (ref "C2") (pin "1") (pinfunction "1_1") (pintype "input"))
      (node (ref "U7") (pin "16") (pinfunction "C_FILT_16") (pintype "unspecified"))
    )
    (net (code "45") (name "Net-(U7-R_EXT)") (class "Default")
      (node (ref "R21") (pin "2") (pinfunction "2_2") (pintype "unspecified"))
      (node (ref "U7") (pin "6") (pinfunction "R_EXT_6") (pintype "unspecified"))
    )
    (net (code "46") (name "R1") (class "Default")
      (node (ref "LED100") (pin "1") (pinfunction "A_1") (pintype "input"))
      (node (ref "LED101") (pin "1") (pinfunction "A_1") (pintype "input"))
      (node (ref "LED102") (pin "1") (pinfunction "A_1") (pintype "input"))
      (node (ref "LED103") (pin "1") (pinfunction "A_1") (pintype "input"))
      (node (ref "LED104") (pin "1") (pinfunction "A_1") (pintype "input"))
      (node (ref "LED105") (pin "1") (pinfunction "A_1") (pintype "input"))
      (node (ref "LED106") (pin "1") (pinfunction "A_1") (pintype "input"))
      (node (ref "LED107") (pin "1") (pinfunction "A_1") (pintype "input"))
      (node (ref "LED108") (pin "1") (pinfunction "A_1") (pintype "input"))
      (node (ref "LED109") (pin "1") (pinfunction "A_1") (pintype "input"))
      (node (ref "LED110") (pin "1") (pinfunction "A_1") (pintype "input"))
      (node (ref "LED112") (pin "1") (pinfunction "A_1") (pintype "input"))
      (node (ref "LED113") (pin "1") (pinfunction "A_1") (pintype "input"))
      (node (ref "LED114") (pin "1") (pinfunction "A_1") (pintype "input"))
      (node (ref "LED115") (pin "1") (pinfunction "A_1") (pintype "input"))
      (node (ref "LED116") (pin "1") (pinfunction "A_1") (pintype "input"))
      (node (ref "LED117") (pin "1") (pinfunction "A_1") (pintype "input"))
      (node (ref "LED118") (pin "1") (pinfunction "A_1") (pintype "input"))
      (node (ref "U6") (pin "7") (pinfunction "CB1_7") (pintype "unspecified"))
      (node (ref "U7") (pin "7") (pinfunction "CB1_7") (pintype "unspecified"))
    )
    (net (code "47") (name "R2") (class "Default")
      (node (ref "LED53") (pin "1") (pinfunction "A_1") (pintype "input"))
      (node (ref "LED54") (pin "1") (pinfunction "A_1") (pintype "input"))
      (node (ref "LED55") (pin "1") (pinfunction "A_1") (pintype "input"))
      (node (ref "LED56") (pin "1") (pinfunction "A_1") (pintype "input"))
      (node (ref "LED57") (pin "1") (pinfunction "A_1") (pintype "input"))
      (node (ref "LED58") (pin "1") (pinfunction "A_1") (pintype "input"))
      (node (ref "LED59") (pin "1") (pinfunction "A_1") (pintype "input"))
      (node (ref "LED60") (pin "1") (pinfunction "A_1") (pintype "input"))
      (node (ref "LED61") (pin "1") (pinfunction "A_1") (pintype "input"))
      (node (ref "LED62") (pin "1") (pinfunction "A_1") (pintype "input"))
      (node (ref "LED63") (pin "1") (pinfunction "A_1") (pintype "input"))
      (node (ref "LED69") (pin "1") (pinfunction "A_1") (pintype "input"))
      (node (ref "LED74") (pin "1") (pinfunction "A_1") (pintype "input"))
      (node (ref "LED79") (pin "1") (pinfunction "A_1") (pintype "input"))
      (node (ref "LED84") (pin "1") (pinfunction "A_1") (pintype "input"))
      (node (ref "LED89") (pin "1") (pinfunction "A_1") (pintype "input"))
      (node (ref "LED94") (pin "1") (pinfunction "A_1") (pintype "input"))
      (node (ref "LED99") (pin "1") (pinfunction "A_1") (pintype "input"))
      (node (ref "U6") (pin "8") (pinfunction "CB2_8") (pintype "unspecified"))
      (node (ref "U7") (pin "8") (pinfunction "CB2_8") (pintype "unspecified"))
    )
    (net (code "48") (name "R3") (class "Default")
      (node (ref "LED12") (pin "1") (pinfunction "A_1") (pintype "input"))
      (node (ref "LED16") (pin "1") (pinfunction "A_1") (pintype "input"))
      (node (ref "LED20") (pin "1") (pinfunction "A_1") (pintype "input"))
      (node (ref "LED24") (pin "1") (pinfunction "A_1") (pintype "input"))
      (node (ref "LED28") (pin "1") (pinfunction "A_1") (pintype "input"))
      (node (ref "LED36") (pin "1") (pinfunction "A_1") (pintype "input"))
      (node (ref "LED4") (pin "1") (pinfunction "A_1") (pintype "input"))
      (node (ref "LED40") (pin "1") (pinfunction "A_1") (pintype "input"))
      (node (ref "LED44") (pin "1") (pinfunction "A_1") (pintype "input"))
      (node (ref "LED48") (pin "1") (pinfunction "A_1") (pintype "input"))
      (node (ref "LED68") (pin "1") (pinfunction "A_1") (pintype "input"))
      (node (ref "LED73") (pin "1") (pinfunction "A_1") (pintype "input"))
      (node (ref "LED78") (pin "1") (pinfunction "A_1") (pintype "input"))
      (node (ref "LED8") (pin "1") (pinfunction "A_1") (pintype "input"))
      (node (ref "LED83") (pin "1") (pinfunction "A_1") (pintype "input"))
      (node (ref "LED88") (pin "1") (pinfunction "A_1") (pintype "input"))
      (node (ref "LED93") (pin "1") (pinfunction "A_1") (pintype "input"))
      (node (ref "LED98") (pin "1") (pinfunction "A_1") (pintype "input"))
      (node (ref "U6") (pin "9") (pinfunction "CB3_9") (pintype "unspecified"))
      (node (ref "U7") (pin "9") (pinfunction "CB3_9") (pintype "unspecified"))
    )
    (net (code "49") (name "R4") (class "Default")
      (node (ref "LED11") (pin "1") (pinfunction "A_1") (pintype "input"))
      (node (ref "LED15") (pin "1") (pinfunction "A_1") (pintype "input"))
      (node (ref "LED19") (pin "1") (pinfunction "A_1") (pintype "input"))
      (node (ref "LED23") (pin "1") (pinfunction "A_1") (pintype "input"))
      (node (ref "LED27") (pin "1") (pinfunction "A_1") (pintype "input"))
      (node (ref "LED3") (pin "1") (pinfunction "A_1") (pintype "input"))
      (node (ref "LED35") (pin "1") (pinfunction "A_1") (pintype "input"))
      (node (ref "LED39") (pin "1") (pinfunction "A_1") (pintype "input"))
      (node (ref "LED43") (pin "1") (pinfunction "A_1") (pintype "input"))
      (node (ref "LED47") (pin "1") (pinfunction "A_1") (pintype "input"))
      (node (ref "LED67") (pin "1") (pinfunction "A_1") (pintype "input"))
      (node (ref "LED7") (pin "1") (pinfunction "A_1") (pintype "input"))
      (node (ref "LED72") (pin "1") (pinfunction "A_1") (pintype "input"))
      (node (ref "LED77") (pin "1") (pinfunction "A_1") (pintype "input"))
      (node (ref "LED82") (pin "1") (pinfunction "A_1") (pintype "input"))
      (node (ref "LED87") (pin "1") (pinfunction "A_1") (pintype "input"))
      (node (ref "LED92") (pin "1") (pinfunction "A_1") (pintype "input"))
      (node (ref "LED97") (pin "1") (pinfunction "A_1") (pintype "input"))
      (node (ref "U6") (pin "10") (pinfunction "CB4_10") (pintype "unspecified"))
      (node (ref "U7") (pin "10") (pinfunction "CB4_10") (pintype "unspecified"))
    )
    (net (code "50") (name "R5") (class "Default")
      (node (ref "LED10") (pin "1") (pinfunction "A_1") (pintype "input"))
      (node (ref "LED14") (pin "1") (pinfunction "A_1") (pintype "input"))
      (node (ref "LED18") (pin "1") (pinfunction "A_1") (pintype "input"))
      (node (ref "LED2") (pin "1") (pinfunction "A_1") (pintype "input"))
      (node (ref "LED22") (pin "1") (pinfunction "A_1") (pintype "input"))
      (node (ref "LED26") (pin "1") (pinfunction "A_1") (pintype "input"))
      (node (ref "LED34") (pin "1") (pinfunction "A_1") (pintype "input"))
      (node (ref "LED38") (pin "1") (pinfunction "A_1") (pintype "input"))
      (node (ref "LED42") (pin "1") (pinfunction "A_1") (pintype "input"))
      (node (ref "LED46") (pin "1") (pinfunction "A_1") (pintype "input"))
      (node (ref "LED6") (pin "1") (pinfunction "A_1") (pintype "input"))
      (node (ref "LED66") (pin "1") (pinfunction "A_1") (pintype "input"))
      (node (ref "LED71") (pin "1") (pinfunction "A_1") (pintype "input"))
      (node (ref "LED76") (pin "1") (pinfunction "A_1") (pintype "input"))
      (node (ref "LED81") (pin "1") (pinfunction "A_1") (pintype "input"))
      (node (ref "LED86") (pin "1") (pinfunction "A_1") (pintype "input"))
      (node (ref "LED91") (pin "1") (pinfunction "A_1") (pintype "input"))
      (node (ref "LED96") (pin "1") (pinfunction "A_1") (pintype "input"))
      (node (ref "U6") (pin "11") (pinfunction "CB5_11") (pintype "unspecified"))
      (node (ref "U7") (pin "11") (pinfunction "CB5_11") (pintype "unspecified"))
    )
    (net (code "51") (name "R6") (class "Default")
      (node (ref "LED1") (pin "1") (pinfunction "A_1") (pintype "input"))
      (node (ref "LED13") (pin "1") (pinfunction "A_1") (pintype "input"))
      (node (ref "LED17") (pin "1") (pinfunction "A_1") (pintype "input"))
      (node (ref "LED21") (pin "1") (pinfunction "A_1") (pintype "input"))
      (node (ref "LED25") (pin "1") (pinfunction "A_1") (pintype "input"))
      (node (ref "LED33") (pin "1") (pinfunction "A_1") (pintype "input"))
      (node (ref "LED37") (pin "1") (pinfunction "A_1") (pintype "input"))
      (node (ref "LED41") (pin "1") (pinfunction "A_1") (pintype "input"))
      (node (ref "LED45") (pin "1") (pinfunction "A_1") (pintype "input"))
      (node (ref "LED5") (pin "1") (pinfunction "A_1") (pintype "input"))
      (node (ref "LED65") (pin "1") (pinfunction "A_1") (pintype "input"))
      (node (ref "LED70") (pin "1") (pinfunction "A_1") (pintype "input"))
      (node (ref "LED75") (pin "1") (pinfunction "A_1") (pintype "input"))
      (node (ref "LED80") (pin "1") (pinfunction "A_1") (pintype "input"))
      (node (ref "LED85") (pin "1") (pinfunction "A_1") (pintype "input"))
      (node (ref "LED9") (pin "1") (pinfunction "A_1") (pintype "input"))
      (node (ref "LED90") (pin "1") (pinfunction "A_1") (pintype "input"))
      (node (ref "LED95") (pin "1") (pinfunction "A_1") (pintype "input"))
      (node (ref "U6") (pin "12") (pinfunction "CB6_12") (pintype "unspecified"))
      (node (ref "U7") (pin "12") (pinfunction "CB6_12") (pintype "unspecified"))
    )
    (net (code "52") (name "VCC") (class "Default")
      (node (ref "C3") (pin "2") (pinfunction "2_2") (pintype "input"))
      (node (ref "U5") (pin "3.3") (pinfunction "3V3_3.3") (pintype "unspecified"))
      (node (ref "U6") (pin "2") (pinfunction "VCC_2") (pintype "unspecified"))
      (node (ref "U6") (pin "3") (pinfunction "SDB_3") (pintype "unspecified"))
      (node (ref "U7") (pin "2") (pinfunction "VCC_2") (pintype "unspecified"))
      (node (ref "U7") (pin "3") (pinfunction "SDB_3") (pintype "unspecified"))
    )
    (net (code "53") (name "unconnected-(U5-GPIO0-Pad0)") (class "Default")
      (node (ref "U5") (pin "0") (pinfunction "GPIO0_0") (pintype "bidirectional"))
    )
    (net (code "54") (name "unconnected-(U5-GPIO1-Pad1)") (class "Default")
      (node (ref "U5") (pin "1") (pinfunction "GPIO1_1") (pintype "bidirectional"))
    )
    (net (code "55") (name "unconnected-(U5-GPIO2-Pad2)") (class "Default")
      (node (ref "U5") (pin "2") (pinfunction "GPIO2_2") (pintype "bidirectional"))
    )
    (net (code "56") (name "unconnected-(U5-GPIO3-Pad3)") (class "Default")
      (node (ref "U5") (pin "3") (pinfunction "GPIO3_3") (pintype "bidirectional"))
    )
    (net (code "57") (name "unconnected-(U5-GPIO4-Pad4)") (class "Default")
      (node (ref "U5") (pin "4") (pinfunction "GPIO4_4") (pintype "bidirectional"))
    )
    (net (code "58") (name "unconnected-(U5-GPIO5-Pad5)") (class "Default")
      (node (ref "U5") (pin "5") (pinfunction "GPIO5_5") (pintype "bidirectional"))
    )
    (net (code "59") (name "unconnected-(U5-GPIO6-Pad6)") (class "Default")
      (node (ref "U5") (pin "6") (pinfunction "GPIO6_6") (pintype "bidirectional"))
    )
    (net (code "60") (name "unconnected-(U5-GPIO7-Pad7)") (class "Default")
      (node (ref "U5") (pin "7") (pinfunction "GPIO7_7") (pintype "bidirectional"))
    )
    (net (code "61") (name "unconnected-(U5-GPIO10-Pad10)") (class "Default")
      (node (ref "U5") (pin "10") (pinfunction "GPIO10_10") (pintype "bidirectional"))
    )
    (net (code "62") (name "unconnected-(U5-GPIO20-Pad20)") (class "Default")
      (node (ref "U5") (pin "20") (pinfunction "GPIO20_20") (pintype "bidirectional"))
    )
    (net (code "63") (name "unconnected-(U5-GPIO21-Pad21)") (class "Default")
      (node (ref "U5") (pin "21") (pinfunction "GPIO21_21") (pintype "bidirectional"))
    )
    (net (code "64") (name "unconnected-(U5-Pad5V)") (class "Default")
      (node (ref "U5") (pin "5V") (pinfunction "5V_5V") (pintype "unspecified"))
    )
    (net (code "65") (name "unconnected-(U6-CB7-Pad13)") (class "Default")
      (node (ref "U6") (pin "13") (pinfunction "CB7_13") (pintype "unspecified"))
    )
    (net (code "66") (name "unconnected-(U6-CB8-Pad14)") (class "Default")
      (node (ref "U6") (pin "14") (pinfunction "CB8_14") (pintype "unspecified"))
    )
    (net (code "67") (name "unconnected-(U6-CB9-Pad15)") (class "Default")
      (node (ref "U6") (pin "15") (pinfunction "CB9_15") (pintype "unspecified"))
    )
    (net (code "68") (name "unconnected-(U6-GND-Pad5)") (class "Default")
      (node (ref "U6") (pin "5") (pinfunction "GND_5") (pintype "unspecified"))
    )
    (net (code "69") (name "unconnected-(U6-IN-Pad17)") (class "Default")
      (node (ref "U6") (pin "17") (pinfunction "IN_17") (pintype "unspecified"))
    )
    (net (code "70") (name "unconnected-(U6-INTB-Pad4)") (class "Default")
      (node (ref "U6") (pin "4") (pinfunction "INTB_4") (pintype "unspecified"))
    )
    (net (code "71") (name "unconnected-(U7-CB7-Pad13)") (class "Default")
      (node (ref "U7") (pin "13") (pinfunction "CB7_13") (pintype "unspecified"))
    )
    (net (code "72") (name "unconnected-(U7-CB8-Pad14)") (class "Default")
      (node (ref "U7") (pin "14") (pinfunction "CB8_14") (pintype "unspecified"))
    )
    (net (code "73") (name "unconnected-(U7-CB9-Pad15)") (class "Default")
      (node (ref "U7") (pin "15") (pinfunction "CB9_15") (pintype "unspecified"))
    )
    (net (code "74") (name "unconnected-(U7-GND-Pad5)") (class "Default")
      (node (ref "U7") (pin "5") (pinfunction "GND_5") (pintype "unspecified"))
    )
    (net (code "75") (name "unconnected-(U7-IN-Pad17)") (class "Default")
      (node (ref "U7") (pin "17") (pinfunction "IN_17") (pintype "unspecified"))
    )
    (net (code "76") (name "unconnected-(U7-INTB-Pad4)") (class "Default")
      (node (ref "U7") (pin "4") (pinfunction "INTB_4") (pintype "unspecified"))
    )
  )
)
